# S7G7_footprint_simplified_w_ethernet_v1p.net
KiCad netlist of a schematic drawn in EAGLE
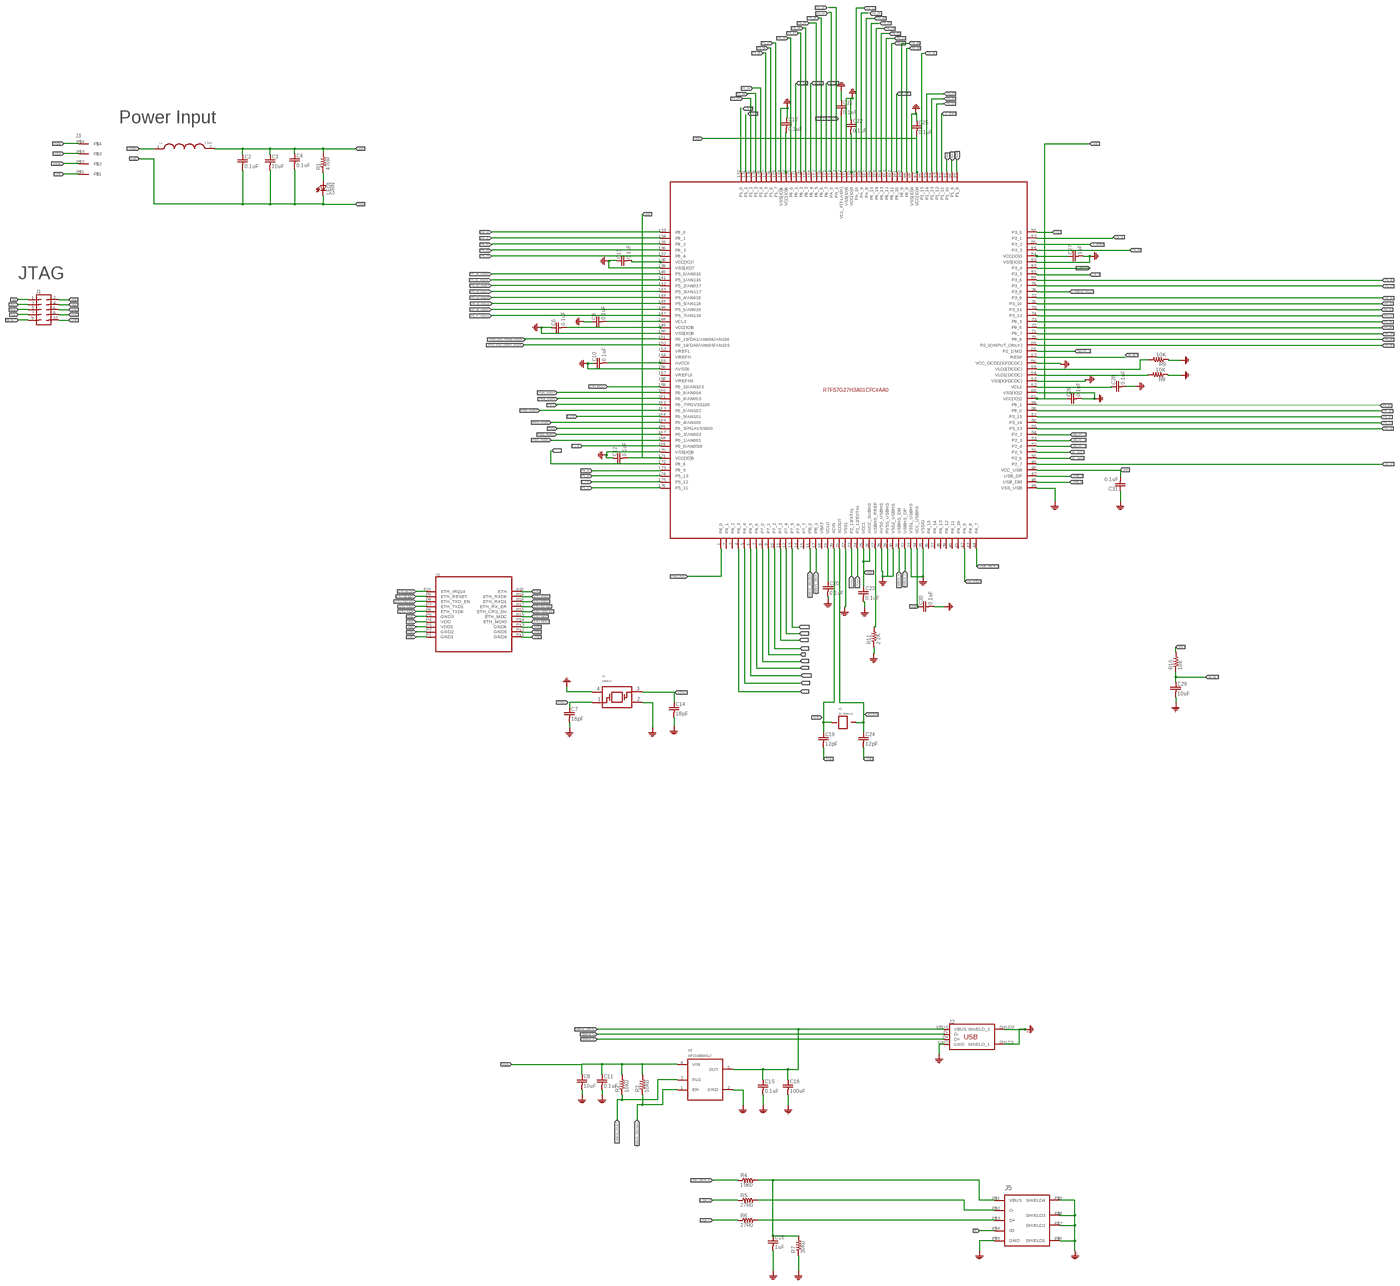
[diagram p0: schematic, sheet 1, overview]
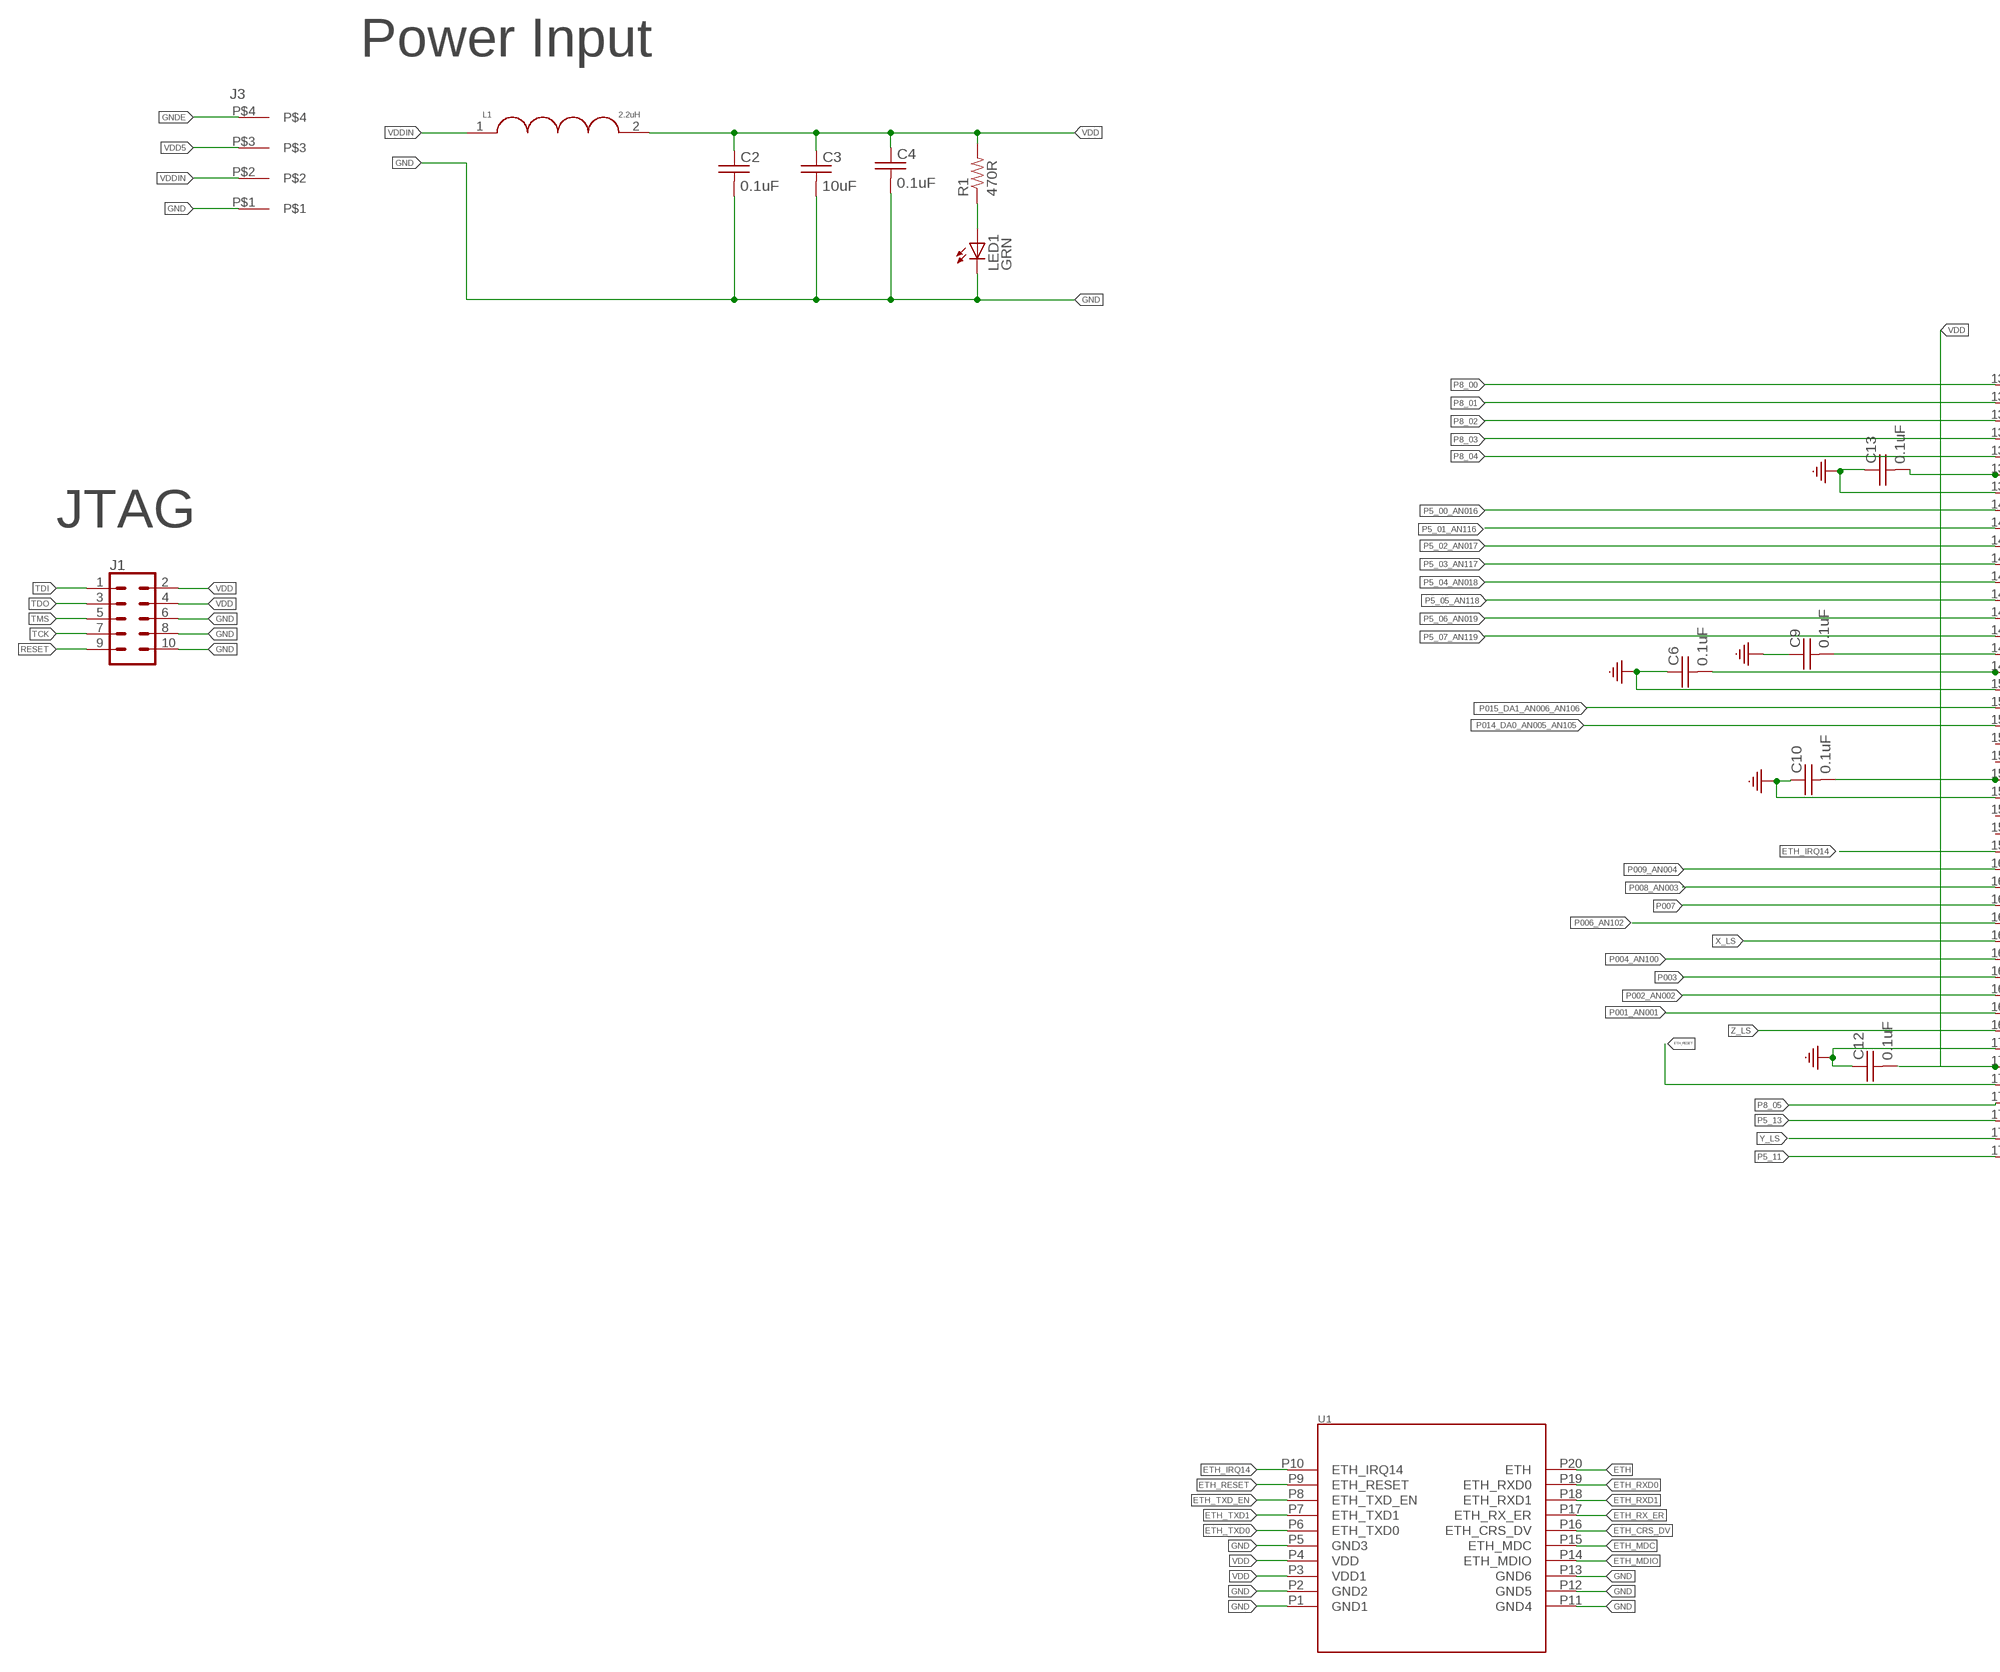
[diagram p1: schematic, sheet 1, part 1 of 4]
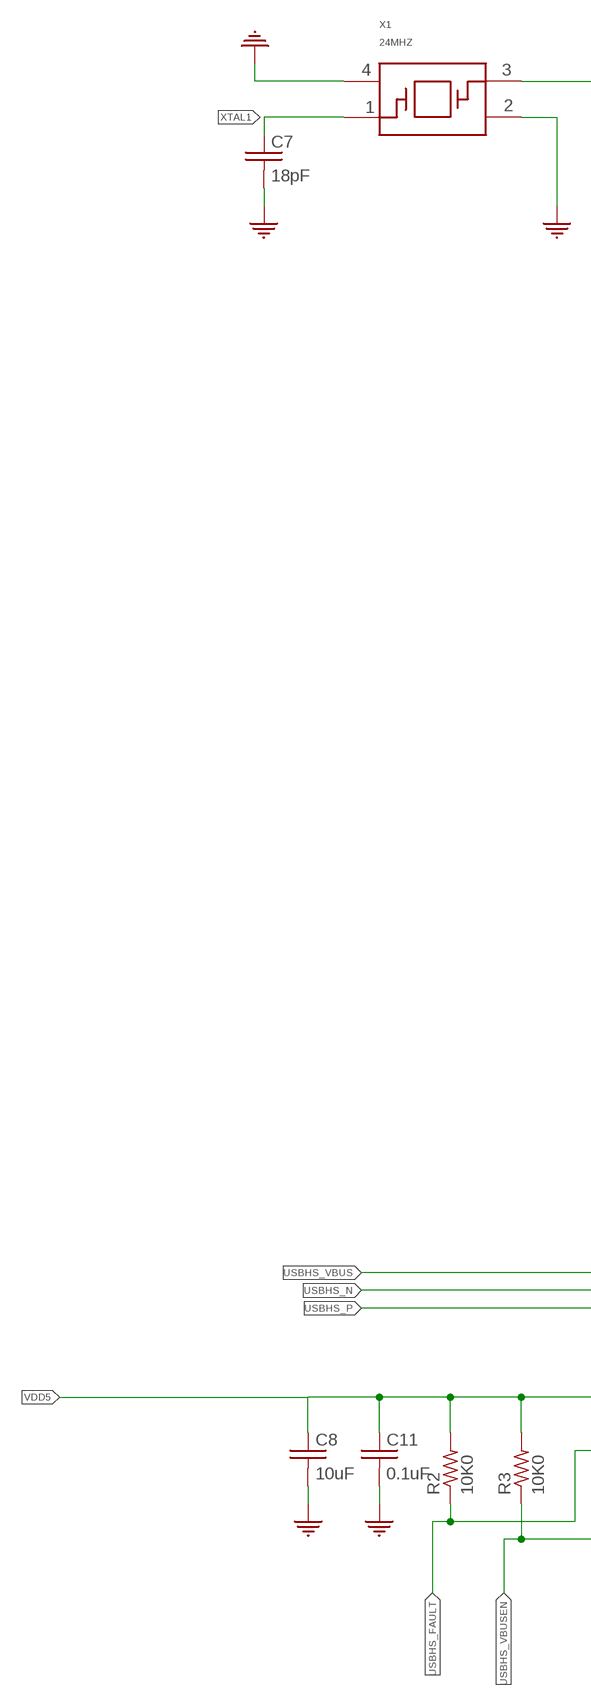
[diagram p2: schematic, sheet 1, part 2 of 4]
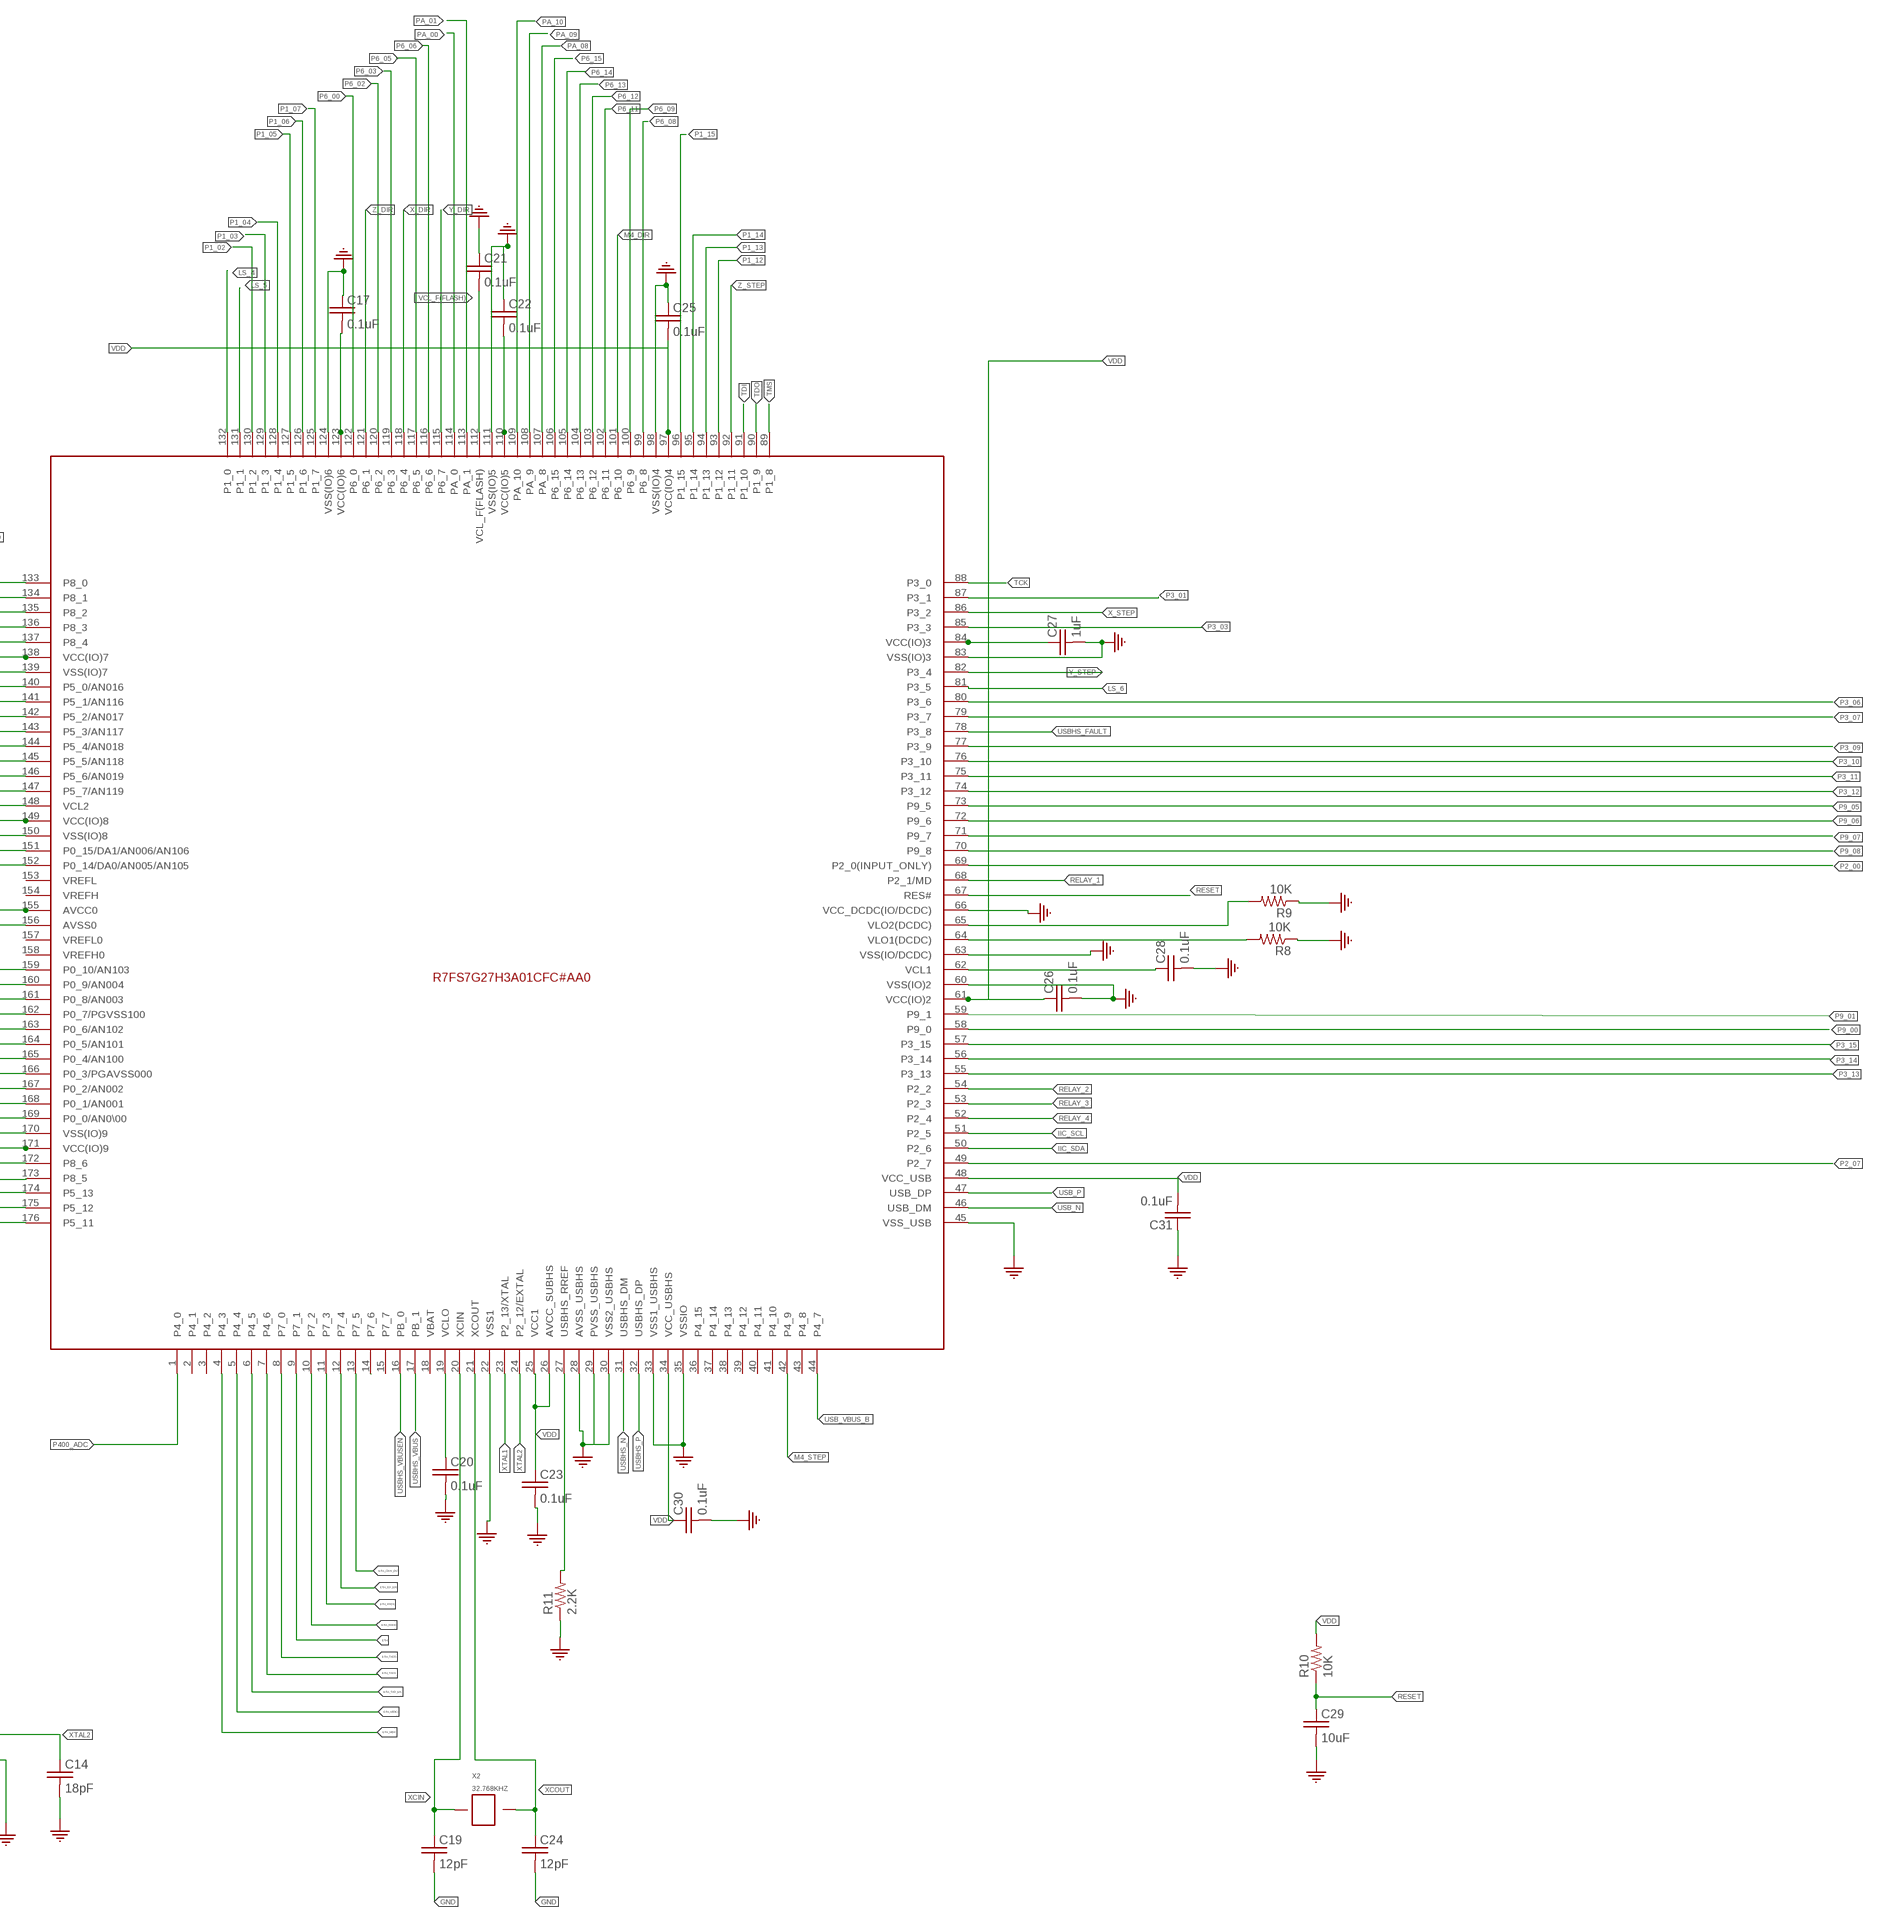
[diagram p3: schematic, sheet 1, part 3 of 4]
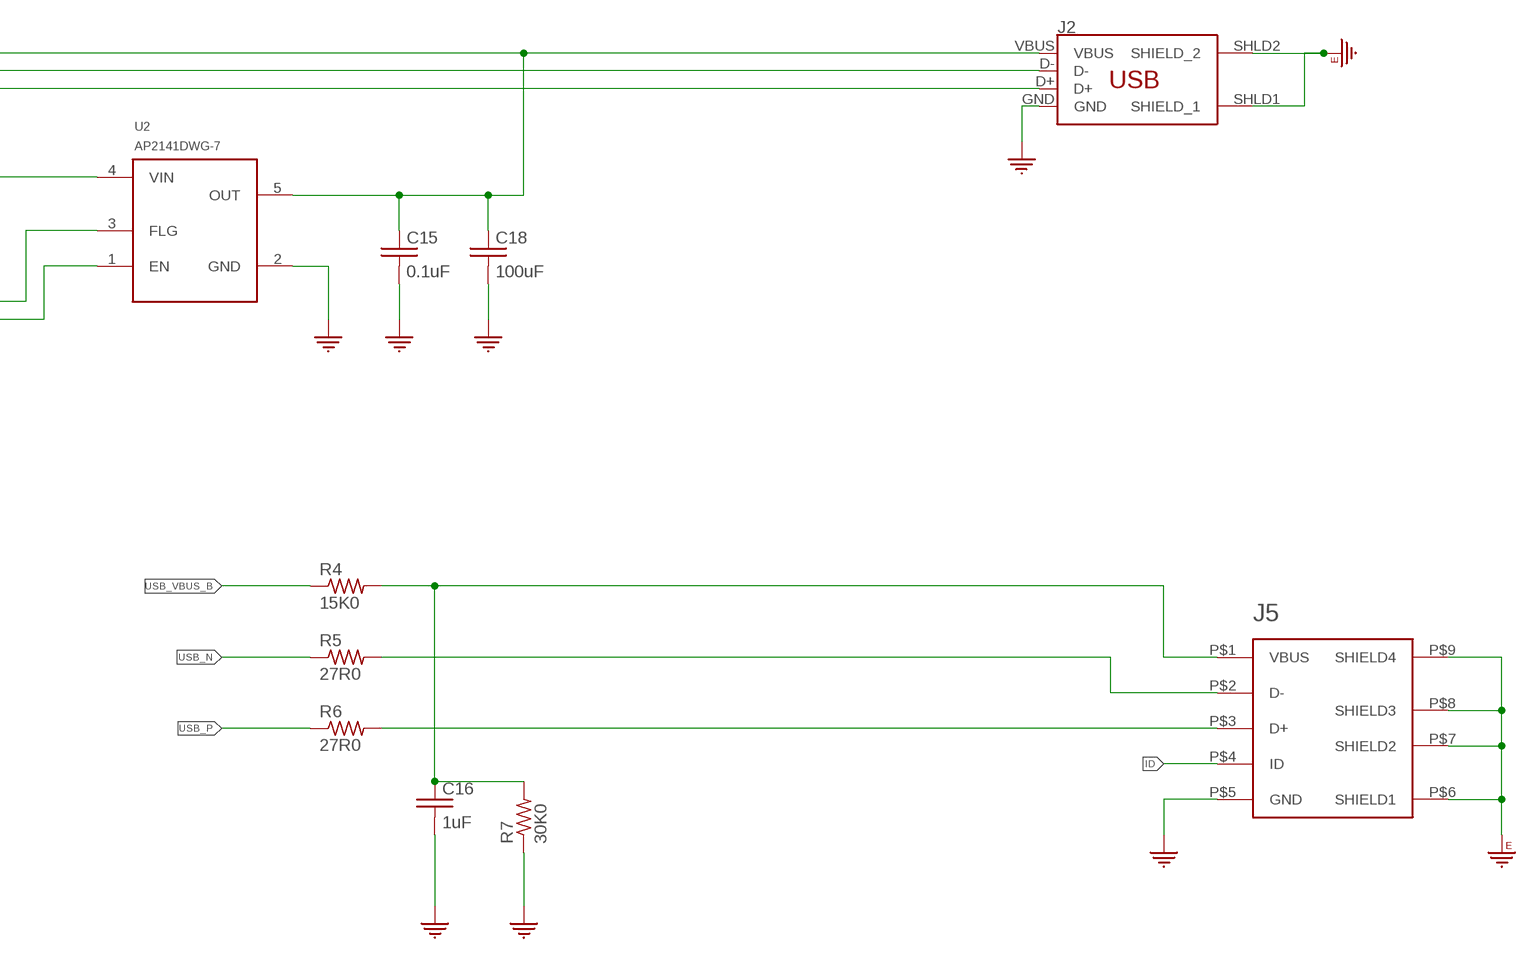
[diagram p4: schematic, sheet 1, part 4 of 4]

(export (version "E")
  (design (tool "Eeschema 10.0.6"))
  (components
    (comp (ref "C2")
      (value "0.1uF")
      (footprint "eagle-import:0402")
      (libsource (lib "eagle-import") (part "C_0402"))
    )
    (comp (ref "C3")
      (value "10uF")
      (footprint "eagle-import:0402")
      (libsource (lib "eagle-import") (part "C_0402"))
    )
    (comp (ref "C4")
      (value "0.1uF")
      (footprint "eagle-import:0402")
      (libsource (lib "eagle-import") (part "C_0402"))
    )
    (comp (ref "C6")
      (value "0.1uF")
      (footprint "eagle-import:0402")
      (libsource (lib "eagle-import") (part "C_0402"))
    )
    (comp (ref "C7")
      (value "18pF")
      (footprint "eagle-import:0402")
      (libsource (lib "eagle-import") (part "C_0402"))
    )
    (comp (ref "C8")
      (value "10uF")
      (footprint "eagle-import:0402")
      (libsource (lib "eagle-import") (part "C_0402"))
    )
    (comp (ref "C9")
      (value "0.1uF")
      (footprint "eagle-import:0402")
      (libsource (lib "eagle-import") (part "C_0402"))
    )
    (comp (ref "C10")
      (value "0.1uF")
      (footprint "eagle-import:0402")
      (libsource (lib "eagle-import") (part "C_0402"))
    )
    (comp (ref "C11")
      (value "0.1uF")
      (footprint "eagle-import:0402")
      (libsource (lib "eagle-import") (part "C_0402"))
    )
    (comp (ref "C12")
      (value "0.1uF")
      (footprint "eagle-import:0402")
      (libsource (lib "eagle-import") (part "C_0402"))
    )
    (comp (ref "C13")
      (value "0.1uF")
      (footprint "eagle-import:0402")
      (libsource (lib "eagle-import") (part "C_0402"))
    )
    (comp (ref "C14")
      (value "18pF")
      (footprint "eagle-import:0402")
      (libsource (lib "eagle-import") (part "C_0402"))
    )
    (comp (ref "C15")
      (value "0.1uF")
      (footprint "eagle-import:0402")
      (libsource (lib "eagle-import") (part "C_0402"))
    )
    (comp (ref "C16")
      (value "1uF")
      (footprint "eagle-import:0402")
      (libsource (lib "eagle-import") (part "C_0402"))
    )
    (comp (ref "C17")
      (value "0.1uF")
      (footprint "eagle-import:0402")
      (libsource (lib "eagle-import") (part "C_0402"))
    )
    (comp (ref "C18")
      (value "100uF")
      (footprint "eagle-import:C1210")
      (libsource (lib "eagle-import") (part "C_1210"))
    )
    (comp (ref "C19")
      (value "12pF")
      (footprint "eagle-import:0402")
      (libsource (lib "eagle-import") (part "C_0402"))
    )
    (comp (ref "C20")
      (value "0.1uF")
      (footprint "eagle-import:0402")
      (libsource (lib "eagle-import") (part "C_0402"))
    )
    (comp (ref "C21")
      (value "0.1uF")
      (footprint "eagle-import:0402")
      (libsource (lib "eagle-import") (part "C_0402"))
    )
    (comp (ref "C22")
      (value "0.1uF")
      (footprint "eagle-import:0402")
      (libsource (lib "eagle-import") (part "C_0402"))
    )
    (comp (ref "C23")
      (value "0.1uF")
      (footprint "eagle-import:0402")
      (libsource (lib "eagle-import") (part "C_0402"))
    )
    (comp (ref "C24")
      (value "12pF")
      (footprint "eagle-import:0402")
      (libsource (lib "eagle-import") (part "C_0402"))
    )
    (comp (ref "C25")
      (value "0.1uF")
      (footprint "eagle-import:0402")
      (libsource (lib "eagle-import") (part "C_0402"))
    )
    (comp (ref "C26")
      (value "0.1uF")
      (footprint "eagle-import:0402")
      (libsource (lib "eagle-import") (part "C_0402"))
    )
    (comp (ref "C27")
      (value "1uF")
      (footprint "eagle-import:0402")
      (libsource (lib "eagle-import") (part "C_0402"))
    )
    (comp (ref "C28")
      (value "0.1uF")
      (footprint "eagle-import:0402")
      (libsource (lib "eagle-import") (part "C_0402"))
    )
    (comp (ref "C29")
      (value "10uF")
      (footprint "eagle-import:0402")
      (libsource (lib "eagle-import") (part "C_0402"))
    )
    (comp (ref "C30")
      (value "0.1uF")
      (footprint "eagle-import:0402")
      (libsource (lib "eagle-import") (part "C_0402"))
    )
    (comp (ref "C31")
      (value "0.1uF")
      (footprint "eagle-import:0402")
      (libsource (lib "eagle-import") (part "C_0402"))
    )
    (comp (ref "J1")
      (value "CONN_05X2PTH")
      (footprint "eagle-import:2X5")
      (libsource (lib "eagle-import") (part "CONN_05X2PTH"))
    )
    (comp (ref "J2")
      (value "USB_A")
      (footprint "eagle-import:USB_A_SMT")
      (libsource (lib "eagle-import") (part "USB_A"))
    )
    (comp (ref "J3")
      (value "3.81MM_1_X_4_RT_ANGLE_PLUG_HEADER")
      (footprint "eagle-import:1X4_3.81MM_PITCH")
      (libsource (lib "eagle-import") (part "3.81MM_1_X_4_RT_ANGLE_PLUG_HEADER"))
    )
    (comp (ref "J5")
      (value "USB_MICRO-B")
      (footprint "eagle-import:USB_MICRO-B")
      (libsource (lib "eagle-import") (part "USB_MICRO-B"))
    )
    (comp (ref "L1")
      (value "2.2uH")
      (footprint "eagle-import:1008_(2520_METRIC)")
      (libsource (lib "eagle-import") (part "INDUCTOR_1008_2.2_MH_1.3A"))
    )
    (comp (ref "LED1")
      (value "LED_0805_GREEN")
      (footprint "eagle-import:LED_0805_GREEN")
      (libsource (lib "eagle-import") (part "LED_0805_GREEN"))
    )
    (comp (ref "R1")
      (value "470R")
      (footprint "eagle-import:0402")
      (libsource (lib "eagle-import") (part "R_0402"))
    )
    (comp (ref "R2")
      (value "10K0")
      (footprint "eagle-import:0402")
      (libsource (lib "eagle-import") (part "R_0402"))
    )
    (comp (ref "R3")
      (value "10K0")
      (footprint "eagle-import:0402")
      (libsource (lib "eagle-import") (part "R_0402"))
    )
    (comp (ref "R4")
      (value "15K0")
      (footprint "eagle-import:0402")
      (libsource (lib "eagle-import") (part "R_0402"))
    )
    (comp (ref "R5")
      (value "27R0")
      (footprint "eagle-import:0402")
      (libsource (lib "eagle-import") (part "R_0402"))
    )
    (comp (ref "R6")
      (value "27R0")
      (footprint "eagle-import:0402")
      (libsource (lib "eagle-import") (part "R_0402"))
    )
    (comp (ref "R7")
      (value "30K0")
      (footprint "eagle-import:0402")
      (libsource (lib "eagle-import") (part "R_0402"))
    )
    (comp (ref "R8")
      (value "10K")
      (footprint "eagle-import:0402")
      (libsource (lib "eagle-import") (part "R_0402"))
    )
    (comp (ref "R9")
      (value "10K")
      (footprint "eagle-import:0402")
      (libsource (lib "eagle-import") (part "R_0402"))
    )
    (comp (ref "R10")
      (value "10K")
      (footprint "eagle-import:0402")
      (libsource (lib "eagle-import") (part "R_0402"))
    )
    (comp (ref "R11")
      (value "2.2K")
      (footprint "eagle-import:0402")
      (libsource (lib "eagle-import") (part "R_0402"))
    )
    (comp (ref "U1")
      (value "ETHERNET_HAT")
      (footprint "eagle-import:ETHERNET_HAT")
      (libsource (lib "eagle-import") (part "ETHERNET_HAT"))
    )
    (comp (ref "U2")
      (value "AP2141DWG-5")
      (footprint "eagle-import:SOT-23-5")
      (libsource (lib "eagle-import") (part "AP2141DWG-5"))
    )
    (comp (ref "U5")
      (value "S7G2_X_176")
      (footprint "eagle-import:LQFP176_24X24")
      (libsource (lib "eagle-import") (part "S7G2_X_176"))
    )
    (comp (ref "X1")
      (value "24MHZ")
      (footprint "eagle-import:SMD_3225")
      (libsource (lib "eagle-import") (part "XTAL_24_MHZ"))
    )
    (comp (ref "X2")
      (value "32.768KHZ")
      (footprint "eagle-import:SMD_X_2_PADS")
      (libsource (lib "eagle-import") (part "XTAL_32.768KHZ"))
    )
  )
  (nets
    (net (code "1") (name "ETH") (class "Default")
      (node (ref "U1") (pin "P20") (pinfunction "ETH_P20") (pintype "bidirectional"))
      (node (ref "U5") (pin "9") (pinfunction "P7_1_9") (pintype "bidirectional"))
    )
    (net (code "2") (name "ETH_CRS_DV") (class "Default")
      (node (ref "U1") (pin "P16") (pinfunction "ETH_CRS_DV_P16") (pintype "bidirectional"))
      (node (ref "U5") (pin "13") (pinfunction "P7_5_13") (pintype "bidirectional"))
    )
    (net (code "3") (name "ETH_IRQ14") (class "Default")
      (node (ref "U1") (pin "P10") (pinfunction "ETH_IRQ14_P10") (pintype "bidirectional"))
      (node (ref "U5") (pin "159") (pinfunction "P0_10/AN103_159") (pintype "bidirectional"))
    )
    (net (code "4") (name "ETH_MDC") (class "Default")
      (node (ref "U1") (pin "P15") (pinfunction "ETH_MDC_P15") (pintype "bidirectional"))
      (node (ref "U5") (pin "4") (pinfunction "P4_3_4") (pintype "bidirectional"))
    )
    (net (code "5") (name "ETH_MDIO") (class "Default")
      (node (ref "U1") (pin "P14") (pinfunction "ETH_MDIO_P14") (pintype "bidirectional"))
      (node (ref "U5") (pin "5") (pinfunction "P4_4_5") (pintype "bidirectional"))
    )
    (net (code "6") (name "ETH_RESET") (class "Default")
      (node (ref "U1") (pin "P9") (pinfunction "ETH_RESET_P9") (pintype "bidirectional"))
      (node (ref "U5") (pin "172") (pinfunction "P8_6_172") (pintype "bidirectional"))
    )
    (net (code "7") (name "ETH_RXD0") (class "Default")
      (node (ref "U1") (pin "P19") (pinfunction "ETH_RXD0_P19") (pintype "bidirectional"))
      (node (ref "U5") (pin "10") (pinfunction "P7_2_10") (pintype "bidirectional"))
    )
    (net (code "8") (name "ETH_RXD1") (class "Default")
      (node (ref "U1") (pin "P18") (pinfunction "ETH_RXD1_P18") (pintype "bidirectional"))
      (node (ref "U5") (pin "11") (pinfunction "P7_3_11") (pintype "bidirectional"))
    )
    (net (code "9") (name "ETH_RX_ER") (class "Default")
      (node (ref "U1") (pin "P17") (pinfunction "ETH_RX_ER_P17") (pintype "bidirectional"))
      (node (ref "U5") (pin "12") (pinfunction "P7_4_12") (pintype "bidirectional"))
    )
    (net (code "10") (name "ETH_TXD0") (class "Default")
      (node (ref "U1") (pin "P6") (pinfunction "ETH_TXD0_P6") (pintype "bidirectional"))
      (node (ref "U5") (pin "8") (pinfunction "P7_0_8") (pintype "bidirectional"))
    )
    (net (code "11") (name "ETH_TXD1") (class "Default")
      (node (ref "U1") (pin "P7") (pinfunction "ETH_TXD1_P7") (pintype "bidirectional"))
      (node (ref "U5") (pin "7") (pinfunction "P4_6_7") (pintype "bidirectional"))
    )
    (net (code "12") (name "ETH_TXD_EN") (class "Default")
      (node (ref "U1") (pin "P8") (pinfunction "ETH_TXD_EN_P8") (pintype "bidirectional"))
      (node (ref "U5") (pin "6") (pinfunction "P4_5_6") (pintype "bidirectional"))
    )
    (net (code "13") (name "GND") (class "Default")
      (node (ref "C10") (pin "P$1") (pinfunction "1_P$1") (pintype "passive"))
      (node (ref "C11") (pin "P$2") (pinfunction "2_P$2") (pintype "passive"))
      (node (ref "C12") (pin "P$1") (pinfunction "1_P$1") (pintype "passive"))
      (node (ref "C13") (pin "P$1") (pinfunction "1_P$1") (pintype "passive"))
      (node (ref "C14") (pin "P$2") (pinfunction "2_P$2") (pintype "passive"))
      (node (ref "C15") (pin "P$2") (pinfunction "2_P$2") (pintype "passive"))
      (node (ref "C16") (pin "P$2") (pinfunction "2_P$2") (pintype "passive"))
      (node (ref "C17") (pin "P$1") (pinfunction "1_P$1") (pintype "passive"))
      (node (ref "C18") (pin "2") (pinfunction "2_2") (pintype "passive"))
      (node (ref "C19") (pin "P$2") (pinfunction "2_P$2") (pintype "passive"))
      (node (ref "C2") (pin "P$2") (pinfunction "2_P$2") (pintype "passive"))
      (node (ref "C20") (pin "P$2") (pinfunction "2_P$2") (pintype "passive"))
      (node (ref "C21") (pin "P$1") (pinfunction "1_P$1") (pintype "passive"))
      (node (ref "C22") (pin "P$1") (pinfunction "1_P$1") (pintype "passive"))
      (node (ref "C23") (pin "P$2") (pinfunction "2_P$2") (pintype "passive"))
      (node (ref "C24") (pin "P$2") (pinfunction "2_P$2") (pintype "passive"))
      (node (ref "C25") (pin "P$1") (pinfunction "1_P$1") (pintype "passive"))
      (node (ref "C26") (pin "P$2") (pinfunction "2_P$2") (pintype "passive"))
      (node (ref "C27") (pin "P$2") (pinfunction "2_P$2") (pintype "passive"))
      (node (ref "C28") (pin "P$2") (pinfunction "2_P$2") (pintype "passive"))
      (node (ref "C29") (pin "P$2") (pinfunction "2_P$2") (pintype "passive"))
      (node (ref "C3") (pin "P$2") (pinfunction "2_P$2") (pintype "passive"))
      (node (ref "C30") (pin "P$2") (pinfunction "2_P$2") (pintype "passive"))
      (node (ref "C31") (pin "P$1") (pinfunction "1_P$1") (pintype "passive"))
      (node (ref "C4") (pin "P$2") (pinfunction "2_P$2") (pintype "passive"))
      (node (ref "C6") (pin "P$1") (pinfunction "1_P$1") (pintype "passive"))
      (node (ref "C7") (pin "P$2") (pinfunction "2_P$2") (pintype "passive"))
      (node (ref "C8") (pin "P$2") (pinfunction "2_P$2") (pintype "passive"))
      (node (ref "C9") (pin "P$1") (pinfunction "1_P$1") (pintype "passive"))
      (node (ref "J1") (pin "10") (pinfunction "10_10") (pintype "passive"))
      (node (ref "J1") (pin "6") (pinfunction "6_6") (pintype "passive"))
      (node (ref "J1") (pin "8") (pinfunction "8_8") (pintype "passive"))
      (node (ref "J2") (pin "GND") (pinfunction "GND_GND") (pintype "power_in"))
      (node (ref "J3") (pin "P$1") (pinfunction "P$1_P$1") (pintype "bidirectional"))
      (node (ref "J5") (pin "P$5") (pinfunction "GND_P$5") (pintype "bidirectional"))
      (node (ref "LED1") (pin "C") (pinfunction "C_C") (pintype "passive"))
      (node (ref "R11") (pin "P$1") (pinfunction "1_P$1") (pintype "passive"))
      (node (ref "R7") (pin "P$1") (pinfunction "1_P$1") (pintype "passive"))
      (node (ref "R8") (pin "P$1") (pinfunction "1_P$1") (pintype "passive"))
      (node (ref "R9") (pin "P$1") (pinfunction "1_P$1") (pintype "passive"))
      (node (ref "U1") (pin "P1") (pinfunction "GND1_P1") (pintype "bidirectional"))
      (node (ref "U1") (pin "P11") (pinfunction "GND4_P11") (pintype "bidirectional"))
      (node (ref "U1") (pin "P12") (pinfunction "GND5_P12") (pintype "bidirectional"))
      (node (ref "U1") (pin "P13") (pinfunction "GND6_P13") (pintype "bidirectional"))
      (node (ref "U1") (pin "P2") (pinfunction "GND2_P2") (pintype "bidirectional"))
      (node (ref "U1") (pin "P5") (pinfunction "GND3_P5") (pintype "bidirectional"))
      (node (ref "U2") (pin "2") (pinfunction "GND_2") (pintype "input"))
      (node (ref "U5") (pin "111") (pinfunction "VSS(IO)5_111") (pintype "bidirectional"))
      (node (ref "U5") (pin "124") (pinfunction "VSS(IO)6_124") (pintype "bidirectional"))
      (node (ref "U5") (pin "139") (pinfunction "VSS(IO)7_139") (pintype "bidirectional"))
      (node (ref "U5") (pin "150") (pinfunction "VSS(IO)8_150") (pintype "bidirectional"))
      (node (ref "U5") (pin "156") (pinfunction "AVSS0_156") (pintype "bidirectional"))
      (node (ref "U5") (pin "170") (pinfunction "VSS(IO)9_170") (pintype "bidirectional"))
      (node (ref "U5") (pin "22") (pinfunction "VSS1_22") (pintype "bidirectional"))
      (node (ref "U5") (pin "28") (pinfunction "AVSS_USBHS_28") (pintype "bidirectional"))
      (node (ref "U5") (pin "29") (pinfunction "PVSS_USBHS_29") (pintype "bidirectional"))
      (node (ref "U5") (pin "30") (pinfunction "VSS2_USBHS_30") (pintype "bidirectional"))
      (node (ref "U5") (pin "33") (pinfunction "VSS1_USBHS_33") (pintype "bidirectional"))
      (node (ref "U5") (pin "35") (pinfunction "VSSIO_35") (pintype "bidirectional"))
      (node (ref "U5") (pin "45") (pinfunction "VSS_USB_45") (pintype "bidirectional"))
      (node (ref "U5") (pin "60") (pinfunction "VSS(IO)2_60") (pintype "bidirectional"))
      (node (ref "U5") (pin "63") (pinfunction "VSS(IO/DCDC)_63") (pintype "bidirectional"))
      (node (ref "U5") (pin "66") (pinfunction "VCC_DCDC(IO/DCDC)_66") (pintype "bidirectional"))
      (node (ref "U5") (pin "83") (pinfunction "VSS(IO)3_83") (pintype "bidirectional"))
      (node (ref "U5") (pin "98") (pinfunction "VSS(IO)4_98") (pintype "bidirectional"))
      (node (ref "X1") (pin "2") (pinfunction "2_2") (pintype "bidirectional"))
      (node (ref "X1") (pin "4") (pinfunction "4_4") (pintype "bidirectional"))
    )
    (net (code "14") (name "GNDE") (class "Default")
      (node (ref "J2") (pin "SHLD1") (pinfunction "SHIELD_1_SHLD1") (pintype "bidirectional"))
      (node (ref "J2") (pin "SHLD2") (pinfunction "SHIELD_2_SHLD2") (pintype "bidirectional"))
      (node (ref "J3") (pin "P$4") (pinfunction "P$4_P$4") (pintype "bidirectional"))
      (node (ref "J5") (pin "P$6") (pinfunction "SHIELD1_P$6") (pintype "bidirectional"))
      (node (ref "J5") (pin "P$7") (pinfunction "SHIELD2_P$7") (pintype "bidirectional"))
      (node (ref "J5") (pin "P$8") (pinfunction "SHIELD3_P$8") (pintype "bidirectional"))
      (node (ref "J5") (pin "P$9") (pinfunction "SHIELD4_P$9") (pintype "bidirectional"))
    )
    (net (code "15") (name "ID") (class "Default")
      (node (ref "J5") (pin "P$4") (pinfunction "ID_P$4") (pintype "bidirectional"))
    )
    (net (code "16") (name "IIC_SCL") (class "Default")
      (node (ref "U5") (pin "51") (pinfunction "P2_5_51") (pintype "bidirectional"))
    )
    (net (code "17") (name "IIC_SDA") (class "Default")
      (node (ref "U5") (pin "50") (pinfunction "P2_6_50") (pintype "bidirectional"))
    )
    (net (code "18") (name "LS_4") (class "Default")
      (node (ref "U5") (pin "132") (pinfunction "P1_0_132") (pintype "bidirectional"))
    )
    (net (code "19") (name "LS_5") (class "Default")
      (node (ref "U5") (pin "131") (pinfunction "P1_1_131") (pintype "bidirectional"))
    )
    (net (code "20") (name "LS_6") (class "Default")
      (node (ref "U5") (pin "81") (pinfunction "P3_5_81") (pintype "bidirectional"))
    )
    (net (code "21") (name "M4_DIR") (class "Default")
      (node (ref "U5") (pin "101") (pinfunction "P6_10_101") (pintype "bidirectional"))
    )
    (net (code "22") (name "M4_STEP") (class "Default")
      (node (ref "U5") (pin "42") (pinfunction "P4_9_42") (pintype "bidirectional"))
    )
    (net (code "23") (name "Net-(C9-2)") (class "Default")
      (node (ref "C9") (pin "P$2") (pinfunction "2_P$2") (pintype "passive"))
      (node (ref "U5") (pin "148") (pinfunction "VCL2_148") (pintype "bidirectional"))
    )
    (net (code "24") (name "Net-(C16-1)") (class "Default")
      (node (ref "C16") (pin "P$1") (pinfunction "1_P$1") (pintype "passive"))
      (node (ref "J5") (pin "P$1") (pinfunction "VBUS_P$1") (pintype "bidirectional"))
      (node (ref "R4") (pin "P$2") (pinfunction "2_P$2") (pintype "passive"))
      (node (ref "R7") (pin "P$2") (pinfunction "2_P$2") (pintype "passive"))
    )
    (net (code "25") (name "Net-(C20-1)") (class "Default")
      (node (ref "C20") (pin "P$1") (pinfunction "1_P$1") (pintype "passive"))
      (node (ref "U5") (pin "19") (pinfunction "VCLO_19") (pintype "bidirectional"))
    )
    (net (code "26") (name "Net-(C28-1)") (class "Default")
      (node (ref "C28") (pin "P$1") (pinfunction "1_P$1") (pintype "passive"))
      (node (ref "U5") (pin "62") (pinfunction "VCL1_62") (pintype "bidirectional"))
    )
    (net (code "27") (name "Net-(J5-D+)") (class "Default")
      (node (ref "J5") (pin "P$3") (pinfunction "D+_P$3") (pintype "bidirectional"))
      (node (ref "R6") (pin "P$2") (pinfunction "2_P$2") (pintype "passive"))
    )
    (net (code "28") (name "Net-(J5-D-)") (class "Default")
      (node (ref "J5") (pin "P$2") (pinfunction "D-_P$2") (pintype "bidirectional"))
      (node (ref "R5") (pin "P$2") (pinfunction "2_P$2") (pintype "passive"))
    )
    (net (code "29") (name "Net-(R1-1)") (class "Default")
      (node (ref "LED1") (pin "A") (pinfunction "A_A") (pintype "passive"))
      (node (ref "R1") (pin "P$1") (pinfunction "1_P$1") (pintype "passive"))
    )
    (net (code "30") (name "Net-(R8-2)") (class "Default")
      (node (ref "R8") (pin "P$2") (pinfunction "2_P$2") (pintype "passive"))
      (node (ref "U5") (pin "64") (pinfunction "VLO1(DCDC)_64") (pintype "bidirectional"))
    )
    (net (code "31") (name "Net-(R9-2)") (class "Default")
      (node (ref "R9") (pin "P$2") (pinfunction "2_P$2") (pintype "passive"))
      (node (ref "U5") (pin "65") (pinfunction "VLO2(DCDC)_65") (pintype "bidirectional"))
    )
    (net (code "32") (name "Net-(R11-2)") (class "Default")
      (node (ref "R11") (pin "P$2") (pinfunction "2_P$2") (pintype "passive"))
      (node (ref "U5") (pin "27") (pinfunction "USBHS_RREF_27") (pintype "bidirectional"))
    )
    (net (code "33") (name "P1_02") (class "Default")
      (node (ref "U5") (pin "130") (pinfunction "P1_2_130") (pintype "bidirectional"))
    )
    (net (code "34") (name "P1_03") (class "Default")
      (node (ref "U5") (pin "129") (pinfunction "P1_3_129") (pintype "bidirectional"))
    )
    (net (code "35") (name "P1_04") (class "Default")
      (node (ref "U5") (pin "128") (pinfunction "P1_4_128") (pintype "bidirectional"))
    )
    (net (code "36") (name "P1_05") (class "Default")
      (node (ref "U5") (pin "127") (pinfunction "P1_5_127") (pintype "bidirectional"))
    )
    (net (code "37") (name "P1_06") (class "Default")
      (node (ref "U5") (pin "126") (pinfunction "P1_6_126") (pintype "bidirectional"))
    )
    (net (code "38") (name "P1_07") (class "Default")
      (node (ref "U5") (pin "125") (pinfunction "P1_7_125") (pintype "bidirectional"))
    )
    (net (code "39") (name "P1_12") (class "Default")
      (node (ref "U5") (pin "93") (pinfunction "P1_12_93") (pintype "bidirectional"))
    )
    (net (code "40") (name "P1_13") (class "Default")
      (node (ref "U5") (pin "94") (pinfunction "P1_13_94") (pintype "bidirectional"))
    )
    (net (code "41") (name "P1_14") (class "Default")
      (node (ref "U5") (pin "95") (pinfunction "P1_14_95") (pintype "bidirectional"))
    )
    (net (code "42") (name "P1_15") (class "Default")
      (node (ref "U5") (pin "96") (pinfunction "P1_15_96") (pintype "bidirectional"))
    )
    (net (code "43") (name "P001_AN001") (class "Default")
      (node (ref "U5") (pin "168") (pinfunction "P0_1/AN001_168") (pintype "bidirectional"))
    )
    (net (code "44") (name "P2_00") (class "Default")
      (node (ref "U5") (pin "69") (pinfunction "P2_0(INPUT_ONLY)_69") (pintype "bidirectional"))
    )
    (net (code "45") (name "P2_07") (class "Default")
      (node (ref "U5") (pin "49") (pinfunction "P2_7_49") (pintype "bidirectional"))
    )
    (net (code "46") (name "P002_AN002") (class "Default")
      (node (ref "U5") (pin "167") (pinfunction "P0_2/AN002_167") (pintype "bidirectional"))
    )
    (net (code "47") (name "P003") (class "Default")
      (node (ref "U5") (pin "166") (pinfunction "P0_3/PGAVSS000_166") (pintype "bidirectional"))
    )
    (net (code "48") (name "P3_01") (class "Default")
      (node (ref "U5") (pin "87") (pinfunction "P3_1_87") (pintype "bidirectional"))
    )
    (net (code "49") (name "P3_03") (class "Default")
      (node (ref "U5") (pin "85") (pinfunction "P3_3_85") (pintype "bidirectional"))
    )
    (net (code "50") (name "P3_06") (class "Default")
      (node (ref "U5") (pin "80") (pinfunction "P3_6_80") (pintype "bidirectional"))
    )
    (net (code "51") (name "P3_07") (class "Default")
      (node (ref "U5") (pin "79") (pinfunction "P3_7_79") (pintype "bidirectional"))
    )
    (net (code "52") (name "P3_09") (class "Default")
      (node (ref "U5") (pin "77") (pinfunction "P3_9_77") (pintype "bidirectional"))
    )
    (net (code "53") (name "P3_10") (class "Default")
      (node (ref "U5") (pin "76") (pinfunction "P3_10_76") (pintype "bidirectional"))
    )
    (net (code "54") (name "P3_11") (class "Default")
      (node (ref "U5") (pin "75") (pinfunction "P3_11_75") (pintype "bidirectional"))
    )
    (net (code "55") (name "P3_12") (class "Default")
      (node (ref "U5") (pin "74") (pinfunction "P3_12_74") (pintype "bidirectional"))
    )
    (net (code "56") (name "P3_13") (class "Default")
      (node (ref "U5") (pin "55") (pinfunction "P3_13_55") (pintype "bidirectional"))
    )
    (net (code "57") (name "P3_14") (class "Default")
      (node (ref "U5") (pin "56") (pinfunction "P3_14_56") (pintype "bidirectional"))
    )
    (net (code "58") (name "P3_15") (class "Default")
      (node (ref "U5") (pin "57") (pinfunction "P3_15_57") (pintype "bidirectional"))
    )
    (net (code "59") (name "P004_AN100") (class "Default")
      (node (ref "U5") (pin "165") (pinfunction "P0_4/AN100_165") (pintype "bidirectional"))
    )
    (net (code "60") (name "P5_00_AN016") (class "Default")
      (node (ref "U5") (pin "140") (pinfunction "P5_0/AN016_140") (pintype "bidirectional"))
    )
    (net (code "61") (name "P5_01_AN116") (class "Default")
      (node (ref "U5") (pin "141") (pinfunction "P5_1/AN116_141") (pintype "bidirectional"))
    )
    (net (code "62") (name "P5_02_AN017") (class "Default")
      (node (ref "U5") (pin "142") (pinfunction "P5_2/AN017_142") (pintype "bidirectional"))
    )
    (net (code "63") (name "P5_03_AN117") (class "Default")
      (node (ref "U5") (pin "143") (pinfunction "P5_3/AN117_143") (pintype "bidirectional"))
    )
    (net (code "64") (name "P5_04_AN018") (class "Default")
      (node (ref "U5") (pin "144") (pinfunction "P5_4/AN018_144") (pintype "bidirectional"))
    )
    (net (code "65") (name "P5_05_AN118") (class "Default")
      (node (ref "U5") (pin "145") (pinfunction "P5_5/AN118_145") (pintype "bidirectional"))
    )
    (net (code "66") (name "P5_06_AN019") (class "Default")
      (node (ref "U5") (pin "146") (pinfunction "P5_6/AN019_146") (pintype "bidirectional"))
    )
    (net (code "67") (name "P5_07_AN119") (class "Default")
      (node (ref "U5") (pin "147") (pinfunction "P5_7/AN119_147") (pintype "bidirectional"))
    )
    (net (code "68") (name "P5_11") (class "Default")
      (node (ref "U5") (pin "176") (pinfunction "P5_11_176") (pintype "bidirectional"))
    )
    (net (code "69") (name "P5_13") (class "Default")
      (node (ref "U5") (pin "174") (pinfunction "P5_13_174") (pintype "bidirectional"))
    )
    (net (code "70") (name "P6_00") (class "Default")
      (node (ref "U5") (pin "122") (pinfunction "P6_0_122") (pintype "bidirectional"))
    )
    (net (code "71") (name "P6_02") (class "Default")
      (node (ref "U5") (pin "120") (pinfunction "P6_2_120") (pintype "bidirectional"))
    )
    (net (code "72") (name "P6_03") (class "Default")
      (node (ref "U5") (pin "119") (pinfunction "P6_3_119") (pintype "bidirectional"))
    )
    (net (code "73") (name "P6_05") (class "Default")
      (node (ref "U5") (pin "117") (pinfunction "P6_5_117") (pintype "bidirectional"))
    )
    (net (code "74") (name "P6_06") (class "Default")
      (node (ref "U5") (pin "116") (pinfunction "P6_6_116") (pintype "bidirectional"))
    )
    (net (code "75") (name "P6_08") (class "Default")
      (node (ref "U5") (pin "99") (pinfunction "P6_8_99") (pintype "bidirectional"))
    )
    (net (code "76") (name "P6_09") (class "Default")
      (node (ref "U5") (pin "100") (pinfunction "P6_9_100") (pintype "bidirectional"))
    )
    (net (code "77") (name "P6_11") (class "Default")
      (node (ref "U5") (pin "102") (pinfunction "P6_11_102") (pintype "bidirectional"))
    )
    (net (code "78") (name "P6_12") (class "Default")
      (node (ref "U5") (pin "103") (pinfunction "P6_12_103") (pintype "bidirectional"))
    )
    (net (code "79") (name "P6_13") (class "Default")
      (node (ref "U5") (pin "104") (pinfunction "P6_13_104") (pintype "bidirectional"))
    )
    (net (code "80") (name "P6_14") (class "Default")
      (node (ref "U5") (pin "105") (pinfunction "P6_14_105") (pintype "bidirectional"))
    )
    (net (code "81") (name "P6_15") (class "Default")
      (node (ref "U5") (pin "106") (pinfunction "P6_15_106") (pintype "bidirectional"))
    )
    (net (code "82") (name "P006_AN102") (class "Default")
      (node (ref "U5") (pin "163") (pinfunction "P0_6/AN102_163") (pintype "bidirectional"))
    )
    (net (code "83") (name "P007") (class "Default")
      (node (ref "U5") (pin "162") (pinfunction "P0_7/PGVSS100_162") (pintype "bidirectional"))
    )
    (net (code "84") (name "P8_00") (class "Default")
      (node (ref "U5") (pin "133") (pinfunction "P8_0_133") (pintype "bidirectional"))
    )
    (net (code "85") (name "P8_01") (class "Default")
      (node (ref "U5") (pin "134") (pinfunction "P8_1_134") (pintype "bidirectional"))
    )
    (net (code "86") (name "P8_02") (class "Default")
      (node (ref "U5") (pin "135") (pinfunction "P8_2_135") (pintype "bidirectional"))
    )
    (net (code "87") (name "P8_03") (class "Default")
      (node (ref "U5") (pin "136") (pinfunction "P8_3_136") (pintype "bidirectional"))
    )
    (net (code "88") (name "P8_04") (class "Default")
      (node (ref "U5") (pin "137") (pinfunction "P8_4_137") (pintype "bidirectional"))
    )
    (net (code "89") (name "P8_05") (class "Default")
      (node (ref "U5") (pin "173") (pinfunction "P8_5_173") (pintype "bidirectional"))
    )
    (net (code "90") (name "P008_AN003") (class "Default")
      (node (ref "U5") (pin "161") (pinfunction "P0_8/AN003_161") (pintype "bidirectional"))
    )
    (net (code "91") (name "P9_00") (class "Default")
      (node (ref "U5") (pin "58") (pinfunction "P9_0_58") (pintype "bidirectional"))
    )
    (net (code "92") (name "P9_01") (class "Default")
      (node (ref "U5") (pin "59") (pinfunction "P9_1_59") (pintype "bidirectional"))
    )
    (net (code "93") (name "P9_05") (class "Default")
      (node (ref "U5") (pin "73") (pinfunction "P9_5_73") (pintype "bidirectional"))
    )
    (net (code "94") (name "P9_06") (class "Default")
      (node (ref "U5") (pin "72") (pinfunction "P9_6_72") (pintype "bidirectional"))
    )
    (net (code "95") (name "P9_07") (class "Default")
      (node (ref "U5") (pin "71") (pinfunction "P9_7_71") (pintype "bidirectional"))
    )
    (net (code "96") (name "P9_08") (class "Default")
      (node (ref "U5") (pin "70") (pinfunction "P9_8_70") (pintype "bidirectional"))
    )
    (net (code "97") (name "P009_AN004") (class "Default")
      (node (ref "U5") (pin "160") (pinfunction "P0_9/AN004_160") (pintype "bidirectional"))
    )
    (net (code "98") (name "P014_DA0_AN005_AN105") (class "Default")
      (node (ref "U5") (pin "152") (pinfunction "P0_14/DA0/AN005/AN105_152") (pintype "bidirectional"))
    )
    (net (code "99") (name "P015_DA1_AN006_AN106") (class "Default")
      (node (ref "U5") (pin "151") (pinfunction "P0_15/DA1/AN006/AN106_151") (pintype "bidirectional"))
    )
    (net (code "100") (name "P400_ADC") (class "Default")
      (node (ref "U5") (pin "1") (pinfunction "P4_0_1") (pintype "bidirectional"))
    )
    (net (code "101") (name "PA_00") (class "Default")
      (node (ref "U5") (pin "114") (pinfunction "PA_0_114") (pintype "bidirectional"))
    )
    (net (code "102") (name "PA_01") (class "Default")
      (node (ref "U5") (pin "113") (pinfunction "PA_1_113") (pintype "bidirectional"))
    )
    (net (code "103") (name "PA_08") (class "Default")
      (node (ref "U5") (pin "107") (pinfunction "PA_8_107") (pintype "bidirectional"))
    )
    (net (code "104") (name "PA_09") (class "Default")
      (node (ref "U5") (pin "108") (pinfunction "PA_9_108") (pintype "bidirectional"))
    )
    (net (code "105") (name "PA_10") (class "Default")
      (node (ref "U5") (pin "109") (pinfunction "PA_10_109") (pintype "bidirectional"))
    )
    (net (code "106") (name "RELAY_1") (class "Default")
      (node (ref "U5") (pin "68") (pinfunction "P2_1/MD_68") (pintype "bidirectional"))
    )
    (net (code "107") (name "RELAY_2") (class "Default")
      (node (ref "U5") (pin "54") (pinfunction "P2_2_54") (pintype "bidirectional"))
    )
    (net (code "108") (name "RELAY_3") (class "Default")
      (node (ref "U5") (pin "53") (pinfunction "P2_3_53") (pintype "bidirectional"))
    )
    (net (code "109") (name "RELAY_4") (class "Default")
      (node (ref "U5") (pin "52") (pinfunction "P2_4_52") (pintype "bidirectional"))
    )
    (net (code "110") (name "RESET") (class "Default")
      (node (ref "C29") (pin "P$1") (pinfunction "1_P$1") (pintype "passive"))
      (node (ref "J1") (pin "9") (pinfunction "9_9") (pintype "passive"))
      (node (ref "R10") (pin "P$1") (pinfunction "1_P$1") (pintype "passive"))
      (node (ref "U5") (pin "67") (pinfunction "RES#_67") (pintype "bidirectional"))
    )
    (net (code "111") (name "TCK") (class "Default")
      (node (ref "J1") (pin "7") (pinfunction "7_7") (pintype "passive"))
      (node (ref "U5") (pin "88") (pinfunction "P3_0_88") (pintype "bidirectional"))
    )
    (net (code "112") (name "TDI") (class "Default")
      (node (ref "J1") (pin "1") (pinfunction "1_1") (pintype "passive"))
      (node (ref "U5") (pin "91") (pinfunction "P1_10_91") (pintype "bidirectional"))
    )
    (net (code "113") (name "TDO") (class "Default")
      (node (ref "J1") (pin "3") (pinfunction "3_3") (pintype "passive"))
      (node (ref "U5") (pin "90") (pinfunction "P1_9_90") (pintype "bidirectional"))
    )
    (net (code "114") (name "TMS") (class "Default")
      (node (ref "J1") (pin "5") (pinfunction "5_5") (pintype "passive"))
      (node (ref "U5") (pin "89") (pinfunction "P1_8_89") (pintype "bidirectional"))
    )
    (net (code "115") (name "USBHS_FAULT") (class "Default")
      (node (ref "R2") (pin "P$1") (pinfunction "1_P$1") (pintype "passive"))
      (node (ref "U2") (pin "3") (pinfunction "FLG_3") (pintype "input"))
      (node (ref "U5") (pin "78") (pinfunction "P3_8_78") (pintype "bidirectional"))
    )
    (net (code "116") (name "USBHS_N") (class "Default")
      (node (ref "J2") (pin "D-") (pinfunction "D-_D-") (pintype "bidirectional"))
      (node (ref "U5") (pin "31") (pinfunction "USBHS_DM_31") (pintype "bidirectional"))
    )
    (net (code "117") (name "USBHS_P") (class "Default")
      (node (ref "J2") (pin "D+") (pinfunction "D+_D+") (pintype "bidirectional"))
      (node (ref "U5") (pin "32") (pinfunction "USBHS_DP_32") (pintype "bidirectional"))
    )
    (net (code "118") (name "USBHS_VBUS") (class "Default")
      (node (ref "C15") (pin "P$1") (pinfunction "1_P$1") (pintype "passive"))
      (node (ref "C18") (pin "1") (pinfunction "1_1") (pintype "passive"))
      (node (ref "J2") (pin "VBUS") (pinfunction "VBUS_VBUS") (pintype "power_in"))
      (node (ref "U2") (pin "5") (pinfunction "OUT_5") (pintype "input"))
      (node (ref "U5") (pin "17") (pinfunction "PB_1_17") (pintype "bidirectional"))
    )
    (net (code "119") (name "USBHS_VBUSEN") (class "Default")
      (node (ref "R3") (pin "P$1") (pinfunction "1_P$1") (pintype "passive"))
      (node (ref "U2") (pin "1") (pinfunction "EN_1") (pintype "input"))
      (node (ref "U5") (pin "16") (pinfunction "PB_0_16") (pintype "bidirectional"))
    )
    (net (code "120") (name "USB_N") (class "Default")
      (node (ref "R5") (pin "P$1") (pinfunction "1_P$1") (pintype "passive"))
      (node (ref "U5") (pin "46") (pinfunction "USB_DM_46") (pintype "bidirectional"))
    )
    (net (code "121") (name "USB_P") (class "Default")
      (node (ref "R6") (pin "P$1") (pinfunction "1_P$1") (pintype "passive"))
      (node (ref "U5") (pin "47") (pinfunction "USB_DP_47") (pintype "bidirectional"))
    )
    (net (code "122") (name "USB_VBUS_B") (class "Default")
      (node (ref "R4") (pin "P$1") (pinfunction "1_P$1") (pintype "passive"))
      (node (ref "U5") (pin "44") (pinfunction "P4_7_44") (pintype "bidirectional"))
    )
    (net (code "123") (name "VCL_F(FLASH)") (class "Default")
      (node (ref "C21") (pin "P$2") (pinfunction "2_P$2") (pintype "passive"))
      (node (ref "U5") (pin "112") (pinfunction "VCL_F(FLASH)_112") (pintype "bidirectional"))
    )
    (net (code "124") (name "VDD") (class "Default")
      (node (ref "C10") (pin "P$2") (pinfunction "2_P$2") (pintype "passive"))
      (node (ref "C12") (pin "P$2") (pinfunction "2_P$2") (pintype "passive"))
      (node (ref "C13") (pin "P$2") (pinfunction "2_P$2") (pintype "passive"))
      (node (ref "C17") (pin "P$2") (pinfunction "2_P$2") (pintype "passive"))
      (node (ref "C2") (pin "P$1") (pinfunction "1_P$1") (pintype "passive"))
      (node (ref "C22") (pin "P$2") (pinfunction "2_P$2") (pintype "passive"))
      (node (ref "C23") (pin "P$1") (pinfunction "1_P$1") (pintype "passive"))
      (node (ref "C25") (pin "P$2") (pinfunction "2_P$2") (pintype "passive"))
      (node (ref "C26") (pin "P$1") (pinfunction "1_P$1") (pintype "passive"))
      (node (ref "C27") (pin "P$1") (pinfunction "1_P$1") (pintype "passive"))
      (node (ref "C3") (pin "P$1") (pinfunction "1_P$1") (pintype "passive"))
      (node (ref "C30") (pin "P$1") (pinfunction "1_P$1") (pintype "passive"))
      (node (ref "C31") (pin "P$2") (pinfunction "2_P$2") (pintype "passive"))
      (node (ref "C4") (pin "P$1") (pinfunction "1_P$1") (pintype "passive"))
      (node (ref "C6") (pin "P$2") (pinfunction "2_P$2") (pintype "passive"))
      (node (ref "J1") (pin "2") (pinfunction "2_2") (pintype "passive"))
      (node (ref "J1") (pin "4") (pinfunction "4_4") (pintype "passive"))
      (node (ref "L1") (pin "2") (pinfunction "P$2_2") (pintype "bidirectional"))
      (node (ref "R1") (pin "P$2") (pinfunction "2_P$2") (pintype "passive"))
      (node (ref "R10") (pin "P$2") (pinfunction "2_P$2") (pintype "passive"))
      (node (ref "U1") (pin "P3") (pinfunction "VDD1_P3") (pintype "bidirectional"))
      (node (ref "U1") (pin "P4") (pinfunction "VDD_P4") (pintype "bidirectional"))
      (node (ref "U5") (pin "110") (pinfunction "VCC(IO)5_110") (pintype "bidirectional"))
      (node (ref "U5") (pin "123") (pinfunction "VCC(IO)6_123") (pintype "bidirectional"))
      (node (ref "U5") (pin "138") (pinfunction "VCC(IO)7_138") (pintype "bidirectional"))
      (node (ref "U5") (pin "149") (pinfunction "VCC(IO)8_149") (pintype "bidirectional"))
      (node (ref "U5") (pin "155") (pinfunction "AVCC0_155") (pintype "bidirectional"))
      (node (ref "U5") (pin "171") (pinfunction "VCC(IO)9_171") (pintype "bidirectional"))
      (node (ref "U5") (pin "25") (pinfunction "VCC1_25") (pintype "bidirectional"))
      (node (ref "U5") (pin "26") (pinfunction "AVCC_SUBHS_26") (pintype "bidirectional"))
      (node (ref "U5") (pin "34") (pinfunction "VCC_USBHS_34") (pintype "bidirectional"))
      (node (ref "U5") (pin "48") (pinfunction "VCC_USB_48") (pintype "bidirectional"))
      (node (ref "U5") (pin "61") (pinfunction "VCC(IO)2_61") (pintype "bidirectional"))
      (node (ref "U5") (pin "84") (pinfunction "VCC(IO)3_84") (pintype "bidirectional"))
      (node (ref "U5") (pin "97") (pinfunction "VCC(IO)4_97") (pintype "bidirectional"))
    )
    (net (code "125") (name "VDD5") (class "Default")
      (node (ref "C11") (pin "P$1") (pinfunction "1_P$1") (pintype "passive"))
      (node (ref "C8") (pin "P$1") (pinfunction "1_P$1") (pintype "passive"))
      (node (ref "J3") (pin "P$3") (pinfunction "P$3_P$3") (pintype "bidirectional"))
      (node (ref "R2") (pin "P$2") (pinfunction "2_P$2") (pintype "passive"))
      (node (ref "R3") (pin "P$2") (pinfunction "2_P$2") (pintype "passive"))
      (node (ref "U2") (pin "4") (pinfunction "VIN_4") (pintype "input"))
    )
    (net (code "126") (name "VDDIN") (class "Default")
      (node (ref "J3") (pin "P$2") (pinfunction "P$2_P$2") (pintype "bidirectional"))
      (node (ref "L1") (pin "1") (pinfunction "P$1_1") (pintype "bidirectional"))
    )
    (net (code "127") (name "XCIN") (class "Default")
      (node (ref "C19") (pin "P$1") (pinfunction "1_P$1") (pintype "passive"))
      (node (ref "U5") (pin "20") (pinfunction "XCIN_20") (pintype "bidirectional"))
      (node (ref "X2") (pin "P$1") (pinfunction "P$1_P$1") (pintype "bidirectional"))
    )
    (net (code "128") (name "XCOUT") (class "Default")
      (node (ref "C24") (pin "P$1") (pinfunction "1_P$1") (pintype "passive"))
      (node (ref "U5") (pin "21") (pinfunction "XCOUT_21") (pintype "bidirectional"))
      (node (ref "X2") (pin "P$2") (pinfunction "P$2_P$2") (pintype "bidirectional"))
    )
    (net (code "129") (name "XTAL1") (class "Default")
      (node (ref "C7") (pin "P$1") (pinfunction "1_P$1") (pintype "passive"))
      (node (ref "U5") (pin "23") (pinfunction "P2_13/XTAL_23") (pintype "bidirectional"))
      (node (ref "X1") (pin "1") (pinfunction "1_1") (pintype "bidirectional"))
    )
    (net (code "130") (name "XTAL2") (class "Default")
      (node (ref "C14") (pin "P$1") (pinfunction "1_P$1") (pintype "passive"))
      (node (ref "U5") (pin "24") (pinfunction "P2_12/EXTAL_24") (pintype "bidirectional"))
      (node (ref "X1") (pin "3") (pinfunction "3_3") (pintype "bidirectional"))
    )
    (net (code "131") (name "X_DIR") (class "Default")
      (node (ref "U5") (pin "118") (pinfunction "P6_4_118") (pintype "bidirectional"))
    )
    (net (code "132") (name "X_LS") (class "Default")
      (node (ref "U5") (pin "164") (pinfunction "P0_5/AN101_164") (pintype "bidirectional"))
    )
    (net (code "133") (name "X_STEP") (class "Default")
      (node (ref "U5") (pin "86") (pinfunction "P3_2_86") (pintype "bidirectional"))
    )
    (net (code "134") (name "Y_DIR") (class "Default")
      (node (ref "U5") (pin "115") (pinfunction "P6_7_115") (pintype "bidirectional"))
    )
    (net (code "135") (name "Y_LS") (class "Default")
      (node (ref "U5") (pin "175") (pinfunction "P5_12_175") (pintype "bidirectional"))
    )
    (net (code "136") (name "Y_STEP") (class "Default")
      (node (ref "U5") (pin "82") (pinfunction "P3_4_82") (pintype "bidirectional"))
    )
    (net (code "137") (name "Z_DIR") (class "Default")
      (node (ref "U5") (pin "121") (pinfunction "P6_1_121") (pintype "bidirectional"))
    )
    (net (code "138") (name "Z_LS") (class "Default")
      (node (ref "U5") (pin "169") (pinfunction "P0_0/AN0\\00_169") (pintype "bidirectional"))
    )
    (net (code "139") (name "Z_STEP") (class "Default")
      (node (ref "U5") (pin "92") (pinfunction "P1_11_92") (pintype "bidirectional"))
    )
    (net (code "140") (name "unconnected-(U5-P4_1-Pad2)") (class "Default")
      (node (ref "U5") (pin "2") (pinfunction "P4_1_2") (pintype "bidirectional"))
    )
    (net (code "141") (name "unconnected-(U5-P4_2-Pad3)") (class "Default")
      (node (ref "U5") (pin "3") (pinfunction "P4_2_3") (pintype "bidirectional"))
    )
    (net (code "142") (name "unconnected-(U5-P4_8-Pad43)") (class "Default")
      (node (ref "U5") (pin "43") (pinfunction "P4_8_43") (pintype "bidirectional"))
    )
    (net (code "143") (name "unconnected-(U5-P4_10-Pad41)") (class "Default")
      (node (ref "U5") (pin "41") (pinfunction "P4_10_41") (pintype "bidirectional"))
    )
    (net (code "144") (name "unconnected-(U5-P4_11-Pad40)") (class "Default")
      (node (ref "U5") (pin "40") (pinfunction "P4_11_40") (pintype "bidirectional"))
    )
    (net (code "145") (name "unconnected-(U5-P4_12-Pad39)") (class "Default")
      (node (ref "U5") (pin "39") (pinfunction "P4_12_39") (pintype "bidirectional"))
    )
    (net (code "146") (name "unconnected-(U5-P4_13-Pad38)") (class "Default")
      (node (ref "U5") (pin "38") (pinfunction "P4_13_38") (pintype "bidirectional"))
    )
    (net (code "147") (name "unconnected-(U5-P4_14-Pad37)") (class "Default")
      (node (ref "U5") (pin "37") (pinfunction "P4_14_37") (pintype "bidirectional"))
    )
    (net (code "148") (name "unconnected-(U5-P4_15-Pad36)") (class "Default")
      (node (ref "U5") (pin "36") (pinfunction "P4_15_36") (pintype "bidirectional"))
    )
    (net (code "149") (name "unconnected-(U5-P7_6-Pad14)") (class "Default")
      (node (ref "U5") (pin "14") (pinfunction "P7_6_14") (pintype "bidirectional"))
    )
    (net (code "150") (name "unconnected-(U5-P7_7-Pad15)") (class "Default")
      (node (ref "U5") (pin "15") (pinfunction "P7_7_15") (pintype "bidirectional"))
    )
    (net (code "151") (name "unconnected-(U5-VBAT-Pad18)") (class "Default")
      (node (ref "U5") (pin "18") (pinfunction "VBAT_18") (pintype "bidirectional"))
    )
    (net (code "152") (name "unconnected-(U5-VREFH-Pad154)") (class "Default")
      (node (ref "U5") (pin "154") (pinfunction "VREFH_154") (pintype "bidirectional"))
    )
    (net (code "153") (name "unconnected-(U5-VREFH0-Pad158)") (class "Default")
      (node (ref "U5") (pin "158") (pinfunction "VREFH0_158") (pintype "bidirectional"))
    )
    (net (code "154") (name "unconnected-(U5-VREFL-Pad153)") (class "Default")
      (node (ref "U5") (pin "153") (pinfunction "VREFL_153") (pintype "bidirectional"))
    )
    (net (code "155") (name "unconnected-(U5-VREFL0-Pad157)") (class "Default")
      (node (ref "U5") (pin "157") (pinfunction "VREFL0_157") (pintype "bidirectional"))
    )
  )
)
